# SCH-MAKEY_MAKEY_PTITTEAM_161002.net
KiCad netlist of a schematic drawn in Altium Designer
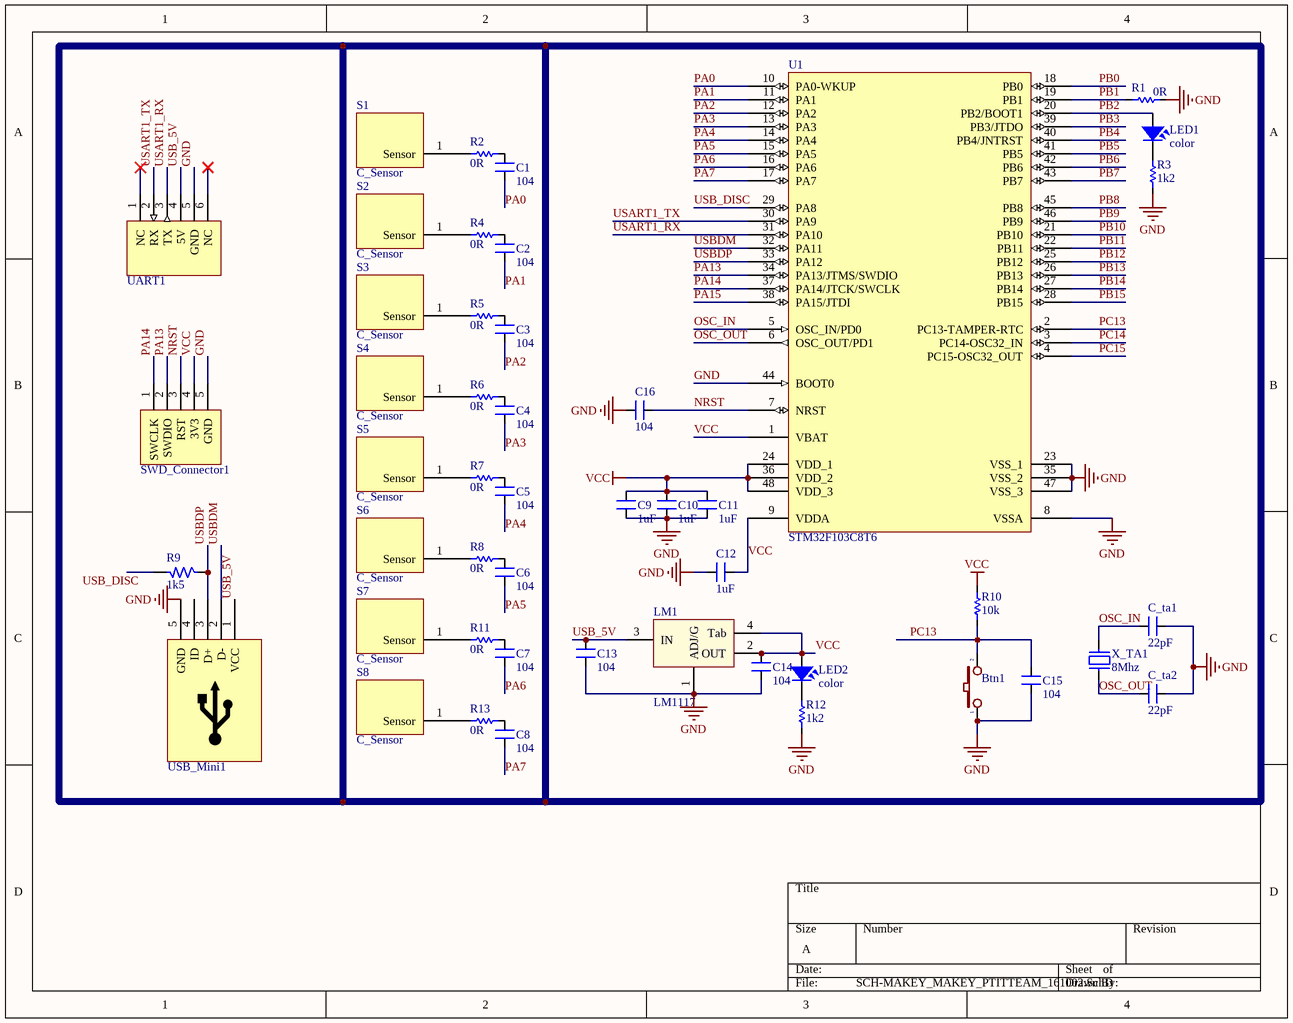
[diagram p0: SCH-MAKEY_MAKEY_PTITTEAM_161002.SchDoc]

(export (version "E")
  (design (tool "Eeschema 10.0.6"))
  (components
    (comp (ref "Btn1")
      (value "Function")
      (footprint "Button_SMD_2pin")
      (description "Switch button 2 pin")
      (libsource (lib "ptit_team_lib") (part "Button_SMD_2pin"))
    )
    (comp (ref "C1")
      (value "104")
      (footprint "CAP_SMD_0603")
      (description "Cap SMD")
      (libsource (lib "syhaunguyen") (part "CM"))
    )
    (comp (ref "C2")
      (value "104")
      (footprint "CAP_SMD_0603")
      (description "Cap SMD")
      (libsource (lib "syhaunguyen") (part "CM"))
    )
    (comp (ref "C3")
      (value "104")
      (footprint "CAP_SMD_0603")
      (description "Cap SMD")
      (libsource (lib "syhaunguyen") (part "CM"))
    )
    (comp (ref "C4")
      (value "104")
      (footprint "CAP_SMD_0603")
      (description "Cap SMD")
      (libsource (lib "syhaunguyen") (part "CM"))
    )
    (comp (ref "C5")
      (value "104")
      (footprint "CAP_SMD_0603")
      (description "Cap SMD")
      (libsource (lib "syhaunguyen") (part "CM"))
    )
    (comp (ref "C6")
      (value "104")
      (footprint "CAP_SMD_0603")
      (description "Cap SMD")
      (libsource (lib "syhaunguyen") (part "CM"))
    )
    (comp (ref "C7")
      (value "104")
      (footprint "CAP_SMD_0603")
      (description "Cremic For Xtal 1pF => 100pF")
      (libsource (lib "syhaunguyen") (part "CN0"))
    )
    (comp (ref "C8")
      (value "104")
      (footprint "CAP_SMD_0603")
      (description "Cremic For Xtal 1pF => 100pF")
      (libsource (lib "syhaunguyen") (part "CN0"))
    )
    (comp (ref "C9")
      (value "1uF")
      (footprint "CAP_SMD_0603")
      (description "Cremic For Xtal 1pF => 100pF")
      (libsource (lib "syhaunguyen") (part "CN0"))
    )
    (comp (ref "C10")
      (value "1uF")
      (footprint "CAP_SMD_0603")
      (description "Cremic For Xtal 1pF => 100pF")
      (libsource (lib "syhaunguyen") (part "CN0"))
    )
    (comp (ref "C11")
      (value "1uF")
      (footprint "CAP_SMD_0603")
      (description "Cap SMD")
      (libsource (lib "syhaunguyen") (part "CM"))
    )
    (comp (ref "C12")
      (value "1uF")
      (footprint "CAP_SMD_0603")
      (description "Cap SMD")
      (libsource (lib "syhaunguyen") (part "CM"))
    )
    (comp (ref "C13")
      (value "104")
      (footprint "CAP_SMD_0603")
      (description "Cap SMD")
      (libsource (lib "syhaunguyen") (part "CM"))
    )
    (comp (ref "C14")
      (value "104")
      (footprint "CAP_SMD_0603")
      (description "Cap SMD")
      (libsource (lib "syhaunguyen") (part "CM"))
    )
    (comp (ref "C15")
      (value "104")
      (footprint "CAP_SMD_0603")
      (description "Cap SMD")
      (libsource (lib "syhaunguyen") (part "CM"))
    )
    (comp (ref "C16")
      (value "104")
      (footprint "CAP_SMD_0603")
      (description "Cap SMD")
      (libsource (lib "syhaunguyen") (part "CM"))
    )
    (comp (ref "C_ta1")
      (value "22pF")
      (footprint "CAP_SMD_0603")
      (description "Cremic For Xtal 1pF => 100pF")
      (libsource (lib "syhaunguyen") (part "CN0"))
    )
    (comp (ref "C_ta2")
      (value "22pF")
      (footprint "CAP_SMD_0603")
      (description "Cremic For Xtal 1pF => 100pF")
      (libsource (lib "syhaunguyen") (part "CN0"))
    )
    (comp (ref "LED1")
      (value "color")
      (footprint "LED_SMD_0805_Yellow")
      (description "Led smd")
      (libsource (lib "ptit_team_lib") (part "Led_SMD"))
    )
    (comp (ref "LED2")
      (value "color")
      (footprint "LED_SMD_0805_Yellow")
      (description "Led smd")
      (libsource (lib "ptit_team_lib") (part "Led_SMD"))
    )
    (comp (ref "LM1")
      (value "LM1117")
      (footprint "SOT223-4N")
      (description "3v3")
      (libsource (lib "syhaunguyen") (part "LM1117"))
    )
    (comp (ref "R1")
      (value "0R")
      (footprint "Res_SMD_0603")
      (description "Resistor smd 0603 type")
      (libsource (lib "ptit_team_lib") (part "Res_SMD_0603"))
    )
    (comp (ref "R2")
      (value "0R")
      (footprint "Res_SMD_0603")
      (description "Resistor smd 0603 type")
      (libsource (lib "ptit_team_lib") (part "Res_SMD_0603"))
    )
    (comp (ref "R3")
      (value "1k2")
      (footprint "Res_SMD_0603")
      (description "Resistor smd 0603 type")
      (libsource (lib "ptit_team_lib") (part "Res_SMD_0603"))
    )
    (comp (ref "R4")
      (value "0R")
      (footprint "Res_SMD_0603")
      (description "Resistor smd 0603 type")
      (libsource (lib "ptit_team_lib") (part "Res_SMD_0603"))
    )
    (comp (ref "R5")
      (value "0R")
      (footprint "Res_SMD_0603")
      (description "Resistor smd 0603 type")
      (libsource (lib "ptit_team_lib") (part "Res_SMD_0603"))
    )
    (comp (ref "R6")
      (value "0R")
      (footprint "Res_SMD_0603")
      (description "Resistor smd 0603 type")
      (libsource (lib "ptit_team_lib") (part "Res_SMD_0603"))
    )
    (comp (ref "R7")
      (value "0R")
      (footprint "Res_SMD_0603")
      (description "Resistor smd 0603 type")
      (libsource (lib "ptit_team_lib") (part "Res_SMD_0603"))
    )
    (comp (ref "R8")
      (value "0R")
      (footprint "Res_SMD_0603")
      (description "Resistor smd 0603 type")
      (libsource (lib "ptit_team_lib") (part "Res_SMD_0603"))
    )
    (comp (ref "R9")
      (value "1k5")
      (footprint "Res_SMD_0603")
      (description "Resistor 1/4W")
      (libsource (lib "syhaunguyen") (part "R"))
    )
    (comp (ref "R10")
      (value "10k")
      (footprint "Res_SMD_0603")
      (description "Resistor smd 0603 type")
      (libsource (lib "ptit_team_lib") (part "Res_SMD_0603"))
    )
    (comp (ref "R11")
      (value "0R")
      (footprint "Res_SMD_0603")
      (description "Resistor smd 0603 type")
      (libsource (lib "ptit_team_lib") (part "Res_SMD_0603"))
    )
    (comp (ref "R12")
      (value "1k2")
      (footprint "Res_SMD_0603")
      (description "Resistor smd 0603 type")
      (libsource (lib "ptit_team_lib") (part "Res_SMD_0603"))
    )
    (comp (ref "R13")
      (value "0R")
      (footprint "Res_SMD_0603")
      (description "Resistor smd 0603 type")
      (libsource (lib "ptit_team_lib") (part "Res_SMD_0603"))
    )
    (comp (ref "S1") (value "C_Sensor") (footprint "SOP2") (libsource (lib "Schlib1") (part "C_Sensor")))
    (comp (ref "S2") (value "C_Sensor") (footprint "SOP2") (libsource (lib "Schlib1") (part "C_Sensor")))
    (comp (ref "S3") (value "C_Sensor") (footprint "SOP2") (libsource (lib "Schlib1") (part "C_Sensor")))
    (comp (ref "S4") (value "C_Sensor") (footprint "SOP2") (libsource (lib "Schlib1") (part "C_Sensor")))
    (comp (ref "S5") (value "C_Sensor") (footprint "SOP2") (libsource (lib "Schlib1") (part "C_Sensor")))
    (comp (ref "S6") (value "C_Sensor") (footprint "SOP2") (libsource (lib "Schlib1") (part "C_Sensor")))
    (comp (ref "S7") (value "C_Sensor") (footprint "SOP2") (libsource (lib "Schlib1") (part "C_Sensor")))
    (comp (ref "S8") (value "C_Sensor") (footprint "SOP2") (libsource (lib "Schlib1") (part "C_Sensor")))
    (comp (ref "SWD_Connector1")
      (value "~")
      (footprint "JP5H")
      (libsource (lib "ptit_team_lib") (part "Load_Program"))
    )
    (comp (ref "U1")
      (value "STM32F103C8T6")
      (footprint "LQFP48_N")
      (description "STM32 ARM-based 32-bit MCU with 64 Kbytes Flash, 48-pin LQFP, Industrial Temperature")
      (fields (field (name "PUBLISHER") "Altium Limited"))
      (libsource (lib "STM32F103C8T6") (part "STM32F103C8T6"))
    )
    (comp (ref "UART1")
      (value "Connector")
      (footprint "JP6H")
      (description "Connector to USB2Com module")
      (libsource (lib "ptit_team_lib") (part "USB2Com_Conn"))
    )
    (comp (ref "USB_Mini1") (value "~") (footprint "Micro_USB") (libsource (lib "ARM") (part "USB_M")))
    (comp (ref "X_TA1")
      (value "8Mhz")
      (footprint "Xtal_SMD")
      (description "Crystal For all Crystal 2pin.")
      (libsource (lib "syhaunguyen") (part "XT2"))
    )
  )
  (nets
    (net (code "1") (name "/NRST") (class "Default")
      (node (ref "C16") (pin "1") (pinfunction "1_1") (pintype "passive"))
      (node (ref "SWD_Connector1") (pin "3") (pinfunction "RST_3") (pintype "open_emitter"))
      (node (ref "U1") (pin "7") (pinfunction "NRST_7") (pintype "bidirectional"))
    )
    (net (code "2") (name "/OSC_IN") (class "Default")
      (node (ref "C_ta1") (pin "1") (pinfunction "1_1") (pintype "passive"))
      (node (ref "U1") (pin "5") (pinfunction "OSC_IN/PD0_5") (pintype "input"))
      (node (ref "X_TA1") (pin "2") (pinfunction "2_2") (pintype "passive"))
    )
    (net (code "3") (name "/OSC_OUT") (class "Default")
      (node (ref "C_ta2") (pin "1") (pinfunction "1_1") (pintype "passive"))
      (node (ref "U1") (pin "6") (pinfunction "OSC_OUT/PD1_6") (pintype "output"))
      (node (ref "X_TA1") (pin "1") (pinfunction "1_1") (pintype "passive"))
    )
    (net (code "4") (name "/PA0") (class "Default")
      (node (ref "C1") (pin "1") (pinfunction "1_1") (pintype "passive"))
      (node (ref "U1") (pin "10") (pinfunction "PA0-WKUP_10") (pintype "bidirectional"))
    )
    (net (code "5") (name "/PA1") (class "Default")
      (node (ref "C2") (pin "1") (pinfunction "1_1") (pintype "passive"))
      (node (ref "U1") (pin "11") (pinfunction "PA1_11") (pintype "bidirectional"))
    )
    (net (code "6") (name "/PA2") (class "Default")
      (node (ref "C3") (pin "1") (pinfunction "1_1") (pintype "passive"))
      (node (ref "U1") (pin "12") (pinfunction "PA2_12") (pintype "bidirectional"))
    )
    (net (code "7") (name "/PA3") (class "Default")
      (node (ref "C4") (pin "1") (pinfunction "1_1") (pintype "passive"))
      (node (ref "U1") (pin "13") (pinfunction "PA3_13") (pintype "bidirectional"))
    )
    (net (code "8") (name "/PA4") (class "Default")
      (node (ref "C5") (pin "1") (pinfunction "1_1") (pintype "passive"))
      (node (ref "U1") (pin "14") (pinfunction "PA4_14") (pintype "bidirectional"))
    )
    (net (code "9") (name "/PA5") (class "Default")
      (node (ref "C6") (pin "1") (pinfunction "1_1") (pintype "passive"))
      (node (ref "U1") (pin "15") (pinfunction "PA5_15") (pintype "bidirectional"))
    )
    (net (code "10") (name "/PA6") (class "Default")
      (node (ref "C7") (pin "1") (pinfunction "1_1") (pintype "passive"))
      (node (ref "U1") (pin "16") (pinfunction "PA6_16") (pintype "bidirectional"))
    )
    (net (code "11") (name "/PA7") (class "Default")
      (node (ref "C8") (pin "1") (pinfunction "1_1") (pintype "passive"))
      (node (ref "U1") (pin "17") (pinfunction "PA7_17") (pintype "bidirectional"))
    )
    (net (code "12") (name "/PA13") (class "Default")
      (node (ref "SWD_Connector1") (pin "2") (pinfunction "SWDIO_2") (pintype "open_emitter"))
      (node (ref "U1") (pin "34") (pinfunction "PA13/JTMS/SWDIO_34") (pintype "bidirectional"))
    )
    (net (code "13") (name "/PA14") (class "Default")
      (node (ref "SWD_Connector1") (pin "1") (pinfunction "SWCLK_1") (pintype "open_emitter"))
      (node (ref "U1") (pin "37") (pinfunction "PA14/JTCK/SWCLK_37") (pintype "bidirectional"))
    )
    (net (code "14") (name "/PA15") (class "Default")
      (node (ref "U1") (pin "38") (pinfunction "PA15/JTDI_38") (pintype "bidirectional"))
    )
    (net (code "15") (name "/PB0") (class "Default")
      (node (ref "U1") (pin "18") (pinfunction "PB0_18") (pintype "bidirectional"))
    )
    (net (code "16") (name "/PB1") (class "Default")
      (node (ref "R1") (pin "2") (pinfunction "2_2") (pintype "passive"))
      (node (ref "U1") (pin "19") (pinfunction "PB1_19") (pintype "bidirectional"))
    )
    (net (code "17") (name "/PB2") (class "Default")
      (node (ref "LED1") (pin "1") (pinfunction "1_1") (pintype "passive"))
      (node (ref "U1") (pin "20") (pinfunction "PB2/BOOT1_20") (pintype "bidirectional"))
    )
    (net (code "18") (name "/PB3") (class "Default")
      (node (ref "U1") (pin "39") (pinfunction "PB3/JTDO_39") (pintype "bidirectional"))
    )
    (net (code "19") (name "/PB4") (class "Default")
      (node (ref "U1") (pin "40") (pinfunction "PB4/JNTRST_40") (pintype "bidirectional"))
    )
    (net (code "20") (name "/PB5") (class "Default")
      (node (ref "U1") (pin "41") (pinfunction "PB5_41") (pintype "bidirectional"))
    )
    (net (code "21") (name "/PB6") (class "Default")
      (node (ref "U1") (pin "42") (pinfunction "PB6_42") (pintype "bidirectional"))
    )
    (net (code "22") (name "/PB7") (class "Default")
      (node (ref "U1") (pin "43") (pinfunction "PB7_43") (pintype "bidirectional"))
    )
    (net (code "23") (name "/PB8") (class "Default")
      (node (ref "U1") (pin "45") (pinfunction "PB8_45") (pintype "bidirectional"))
    )
    (net (code "24") (name "/PB9") (class "Default")
      (node (ref "U1") (pin "46") (pinfunction "PB9_46") (pintype "bidirectional"))
    )
    (net (code "25") (name "/PB10") (class "Default")
      (node (ref "U1") (pin "21") (pinfunction "PB10_21") (pintype "bidirectional"))
    )
    (net (code "26") (name "/PB11") (class "Default")
      (node (ref "U1") (pin "22") (pinfunction "PB11_22") (pintype "bidirectional"))
    )
    (net (code "27") (name "/PB12") (class "Default")
      (node (ref "U1") (pin "25") (pinfunction "PB12_25") (pintype "bidirectional"))
    )
    (net (code "28") (name "/PB13") (class "Default")
      (node (ref "U1") (pin "26") (pinfunction "PB13_26") (pintype "bidirectional"))
    )
    (net (code "29") (name "/PB14") (class "Default")
      (node (ref "U1") (pin "27") (pinfunction "PB14_27") (pintype "bidirectional"))
    )
    (net (code "30") (name "/PB15") (class "Default")
      (node (ref "U1") (pin "28") (pinfunction "PB15_28") (pintype "bidirectional"))
    )
    (net (code "31") (name "/PC13") (class "Default")
      (node (ref "Btn1") (pin "2") (pinfunction "2_2") (pintype "passive"))
      (node (ref "C15") (pin "2") (pinfunction "2_2") (pintype "passive"))
      (node (ref "R10") (pin "1") (pinfunction "1_1") (pintype "passive"))
      (node (ref "U1") (pin "2") (pinfunction "PC13-TAMPER-RTC_2") (pintype "bidirectional"))
    )
    (net (code "32") (name "/PC14") (class "Default")
      (node (ref "U1") (pin "3") (pinfunction "PC14-OSC32_IN_3") (pintype "bidirectional"))
    )
    (net (code "33") (name "/PC15") (class "Default")
      (node (ref "U1") (pin "4") (pinfunction "PC15-OSC32_OUT_4") (pintype "bidirectional"))
    )
    (net (code "34") (name "/USART1_RX") (class "Default")
      (node (ref "U1") (pin "31") (pinfunction "PA10_31") (pintype "bidirectional"))
      (node (ref "UART1") (pin "3") (pinfunction "TX_3") (pintype "output"))
    )
    (net (code "35") (name "/USART1_TX") (class "Default")
      (node (ref "U1") (pin "30") (pinfunction "PA9_30") (pintype "bidirectional"))
      (node (ref "UART1") (pin "2") (pinfunction "RX_2") (pintype "input"))
    )
    (net (code "36") (name "/USBDM") (class "Default")
      (node (ref "U1") (pin "32") (pinfunction "PA11_32") (pintype "bidirectional"))
      (node (ref "USB_Mini1") (pin "2") (pinfunction "D-_2") (pintype "passive"))
    )
    (net (code "37") (name "/USBDP") (class "Default")
      (node (ref "R9") (pin "1") (pinfunction "1_1") (pintype "passive"))
      (node (ref "U1") (pin "33") (pinfunction "PA12_33") (pintype "bidirectional"))
      (node (ref "USB_Mini1") (pin "3") (pinfunction "D+_3") (pintype "passive"))
    )
    (net (code "38") (name "/USB_5V") (class "Default")
      (node (ref "C13") (pin "2") (pinfunction "2_2") (pintype "passive"))
      (node (ref "LM1") (pin "3") (pinfunction "IN_3") (pintype "passive"))
      (node (ref "UART1") (pin "4") (pinfunction "5V_4") (pintype "power_in"))
      (node (ref "USB_Mini1") (pin "1") (pinfunction "VCC_1") (pintype "passive"))
    )
    (net (code "39") (name "/USB_DISC") (class "Default")
      (node (ref "R9") (pin "2") (pinfunction "2_2") (pintype "passive"))
      (node (ref "U1") (pin "29") (pinfunction "PA8_29") (pintype "bidirectional"))
    )
    (net (code "40") (name "GND") (class "Default")
      (node (ref "Btn1") (pin "1") (pinfunction "1_1") (pintype "passive"))
      (node (ref "C10") (pin "2") (pinfunction "2_2") (pintype "passive"))
      (node (ref "C11") (pin "1") (pinfunction "1_1") (pintype "passive"))
      (node (ref "C12") (pin "2") (pinfunction "2_2") (pintype "passive"))
      (node (ref "C13") (pin "1") (pinfunction "1_1") (pintype "passive"))
      (node (ref "C14") (pin "1") (pinfunction "1_1") (pintype "passive"))
      (node (ref "C15") (pin "1") (pinfunction "1_1") (pintype "passive"))
      (node (ref "C16") (pin "2") (pinfunction "2_2") (pintype "passive"))
      (node (ref "C9") (pin "1") (pinfunction "1_1") (pintype "passive"))
      (node (ref "C_ta1") (pin "2") (pinfunction "2_2") (pintype "passive"))
      (node (ref "C_ta2") (pin "2") (pinfunction "2_2") (pintype "passive"))
      (node (ref "LM1") (pin "1") (pinfunction "ADJ/G_1") (pintype "passive"))
      (node (ref "R1") (pin "1") (pinfunction "1_1") (pintype "passive"))
      (node (ref "R12") (pin "1") (pinfunction "1_1") (pintype "passive"))
      (node (ref "R3") (pin "1") (pinfunction "1_1") (pintype "passive"))
      (node (ref "SWD_Connector1") (pin "5") (pinfunction "GND_5") (pintype "power_in"))
      (node (ref "U1") (pin "23") (pinfunction "VSS_1_23") (pintype "power_in"))
      (node (ref "U1") (pin "35") (pinfunction "VSS_2_35") (pintype "power_in"))
      (node (ref "U1") (pin "44") (pinfunction "BOOT0_44") (pintype "input"))
      (node (ref "U1") (pin "47") (pinfunction "VSS_3_47") (pintype "power_in"))
      (node (ref "U1") (pin "8") (pinfunction "VSSA_8") (pintype "power_in"))
      (node (ref "UART1") (pin "5") (pinfunction "GND_5") (pintype "power_in"))
      (node (ref "USB_Mini1") (pin "5") (pinfunction "GND_5") (pintype "passive"))
    )
    (net (code "41") (name "Net-(C1-Pad2)") (class "Default")
      (node (ref "C1") (pin "2") (pinfunction "2_2") (pintype "passive"))
      (node (ref "R2") (pin "1") (pinfunction "1_1") (pintype "passive"))
    )
    (net (code "42") (name "Net-(C2-Pad2)") (class "Default")
      (node (ref "C2") (pin "2") (pinfunction "2_2") (pintype "passive"))
      (node (ref "R4") (pin "1") (pinfunction "1_1") (pintype "passive"))
    )
    (net (code "43") (name "Net-(C3-Pad2)") (class "Default")
      (node (ref "C3") (pin "2") (pinfunction "2_2") (pintype "passive"))
      (node (ref "R5") (pin "1") (pinfunction "1_1") (pintype "passive"))
    )
    (net (code "44") (name "Net-(C4-Pad2)") (class "Default")
      (node (ref "C4") (pin "2") (pinfunction "2_2") (pintype "passive"))
      (node (ref "R6") (pin "1") (pinfunction "1_1") (pintype "passive"))
    )
    (net (code "45") (name "Net-(C5-Pad2)") (class "Default")
      (node (ref "C5") (pin "2") (pinfunction "2_2") (pintype "passive"))
      (node (ref "R7") (pin "1") (pinfunction "1_1") (pintype "passive"))
    )
    (net (code "46") (name "Net-(C6-Pad2)") (class "Default")
      (node (ref "C6") (pin "2") (pinfunction "2_2") (pintype "passive"))
      (node (ref "R8") (pin "1") (pinfunction "1_1") (pintype "passive"))
    )
    (net (code "47") (name "Net-(C7-Pad2)") (class "Default")
      (node (ref "C7") (pin "2") (pinfunction "2_2") (pintype "passive"))
      (node (ref "R11") (pin "1") (pinfunction "1_1") (pintype "passive"))
    )
    (net (code "48") (name "Net-(C8-Pad2)") (class "Default")
      (node (ref "C8") (pin "2") (pinfunction "2_2") (pintype "passive"))
      (node (ref "R13") (pin "1") (pinfunction "1_1") (pintype "passive"))
    )
    (net (code "49") (name "Net-(LED1-Pad2)") (class "Default")
      (node (ref "LED1") (pin "2") (pinfunction "2_2") (pintype "passive"))
      (node (ref "R3") (pin "2") (pinfunction "2_2") (pintype "passive"))
    )
    (net (code "50") (name "Net-(LED2-Pad2)") (class "Default")
      (node (ref "LED2") (pin "2") (pinfunction "2_2") (pintype "passive"))
      (node (ref "R12") (pin "2") (pinfunction "2_2") (pintype "passive"))
    )
    (net (code "51") (name "Net-(S1-Sensor)") (class "Default")
      (node (ref "R2") (pin "2") (pinfunction "2_2") (pintype "passive"))
      (node (ref "S1") (pin "1") (pinfunction "Sensor_1") (pintype "passive"))
    )
    (net (code "52") (name "Net-(S2-Sensor)") (class "Default")
      (node (ref "R4") (pin "2") (pinfunction "2_2") (pintype "passive"))
      (node (ref "S2") (pin "1") (pinfunction "Sensor_1") (pintype "passive"))
    )
    (net (code "53") (name "Net-(S3-Sensor)") (class "Default")
      (node (ref "R5") (pin "2") (pinfunction "2_2") (pintype "passive"))
      (node (ref "S3") (pin "1") (pinfunction "Sensor_1") (pintype "passive"))
    )
    (net (code "54") (name "Net-(S4-Sensor)") (class "Default")
      (node (ref "R6") (pin "2") (pinfunction "2_2") (pintype "passive"))
      (node (ref "S4") (pin "1") (pinfunction "Sensor_1") (pintype "passive"))
    )
    (net (code "55") (name "Net-(S5-Sensor)") (class "Default")
      (node (ref "R7") (pin "2") (pinfunction "2_2") (pintype "passive"))
      (node (ref "S5") (pin "1") (pinfunction "Sensor_1") (pintype "passive"))
    )
    (net (code "56") (name "Net-(S6-Sensor)") (class "Default")
      (node (ref "R8") (pin "2") (pinfunction "2_2") (pintype "passive"))
      (node (ref "S6") (pin "1") (pinfunction "Sensor_1") (pintype "passive"))
    )
    (net (code "57") (name "Net-(S7-Sensor)") (class "Default")
      (node (ref "R11") (pin "2") (pinfunction "2_2") (pintype "passive"))
      (node (ref "S7") (pin "1") (pinfunction "Sensor_1") (pintype "passive"))
    )
    (net (code "58") (name "Net-(S8-Sensor)") (class "Default")
      (node (ref "R13") (pin "2") (pinfunction "2_2") (pintype "passive"))
      (node (ref "S8") (pin "1") (pinfunction "Sensor_1") (pintype "passive"))
    )
    (net (code "59") (name "VCC") (class "Default")
      (node (ref "C10") (pin "1") (pinfunction "1_1") (pintype "passive"))
      (node (ref "C11") (pin "2") (pinfunction "2_2") (pintype "passive"))
      (node (ref "C12") (pin "1") (pinfunction "1_1") (pintype "passive"))
      (node (ref "C14") (pin "2") (pinfunction "2_2") (pintype "passive"))
      (node (ref "C9") (pin "2") (pinfunction "2_2") (pintype "passive"))
      (node (ref "LED2") (pin "1") (pinfunction "1_1") (pintype "passive"))
      (node (ref "LM1") (pin "2") (pinfunction "OUT_2") (pintype "passive"))
      (node (ref "LM1") (pin "4") (pinfunction "Tab_4") (pintype "passive"))
      (node (ref "R10") (pin "2") (pinfunction "2_2") (pintype "passive"))
      (node (ref "SWD_Connector1") (pin "4") (pinfunction "3V3_4") (pintype "power_in"))
      (node (ref "U1") (pin "1") (pinfunction "VBAT_1") (pintype "power_in"))
      (node (ref "U1") (pin "24") (pinfunction "VDD_1_24") (pintype "power_in"))
      (node (ref "U1") (pin "36") (pinfunction "VDD_2_36") (pintype "power_in"))
      (node (ref "U1") (pin "48") (pinfunction "VDD_3_48") (pintype "power_in"))
      (node (ref "U1") (pin "9") (pinfunction "VDDA_9") (pintype "power_in"))
    )
    (net (code "60") (name "unconnected-(UART1-NC-Pad1)") (class "Default")
      (node (ref "UART1") (pin "1") (pinfunction "NC_1") (pintype "passive+no_connect"))
    )
    (net (code "61") (name "unconnected-(UART1-NC-Pad6)") (class "Default")
      (node (ref "UART1") (pin "6") (pinfunction "NC_6") (pintype "passive+no_connect"))
    )
    (net (code "62") (name "unconnected-(USB_Mini1-ID-Pad4)") (class "Default")
      (node (ref "USB_Mini1") (pin "4") (pinfunction "ID_4") (pintype "passive"))
    )
  )
)
